# RTCRpi.net
KiCad netlist of a schematic drawn in EAGLE
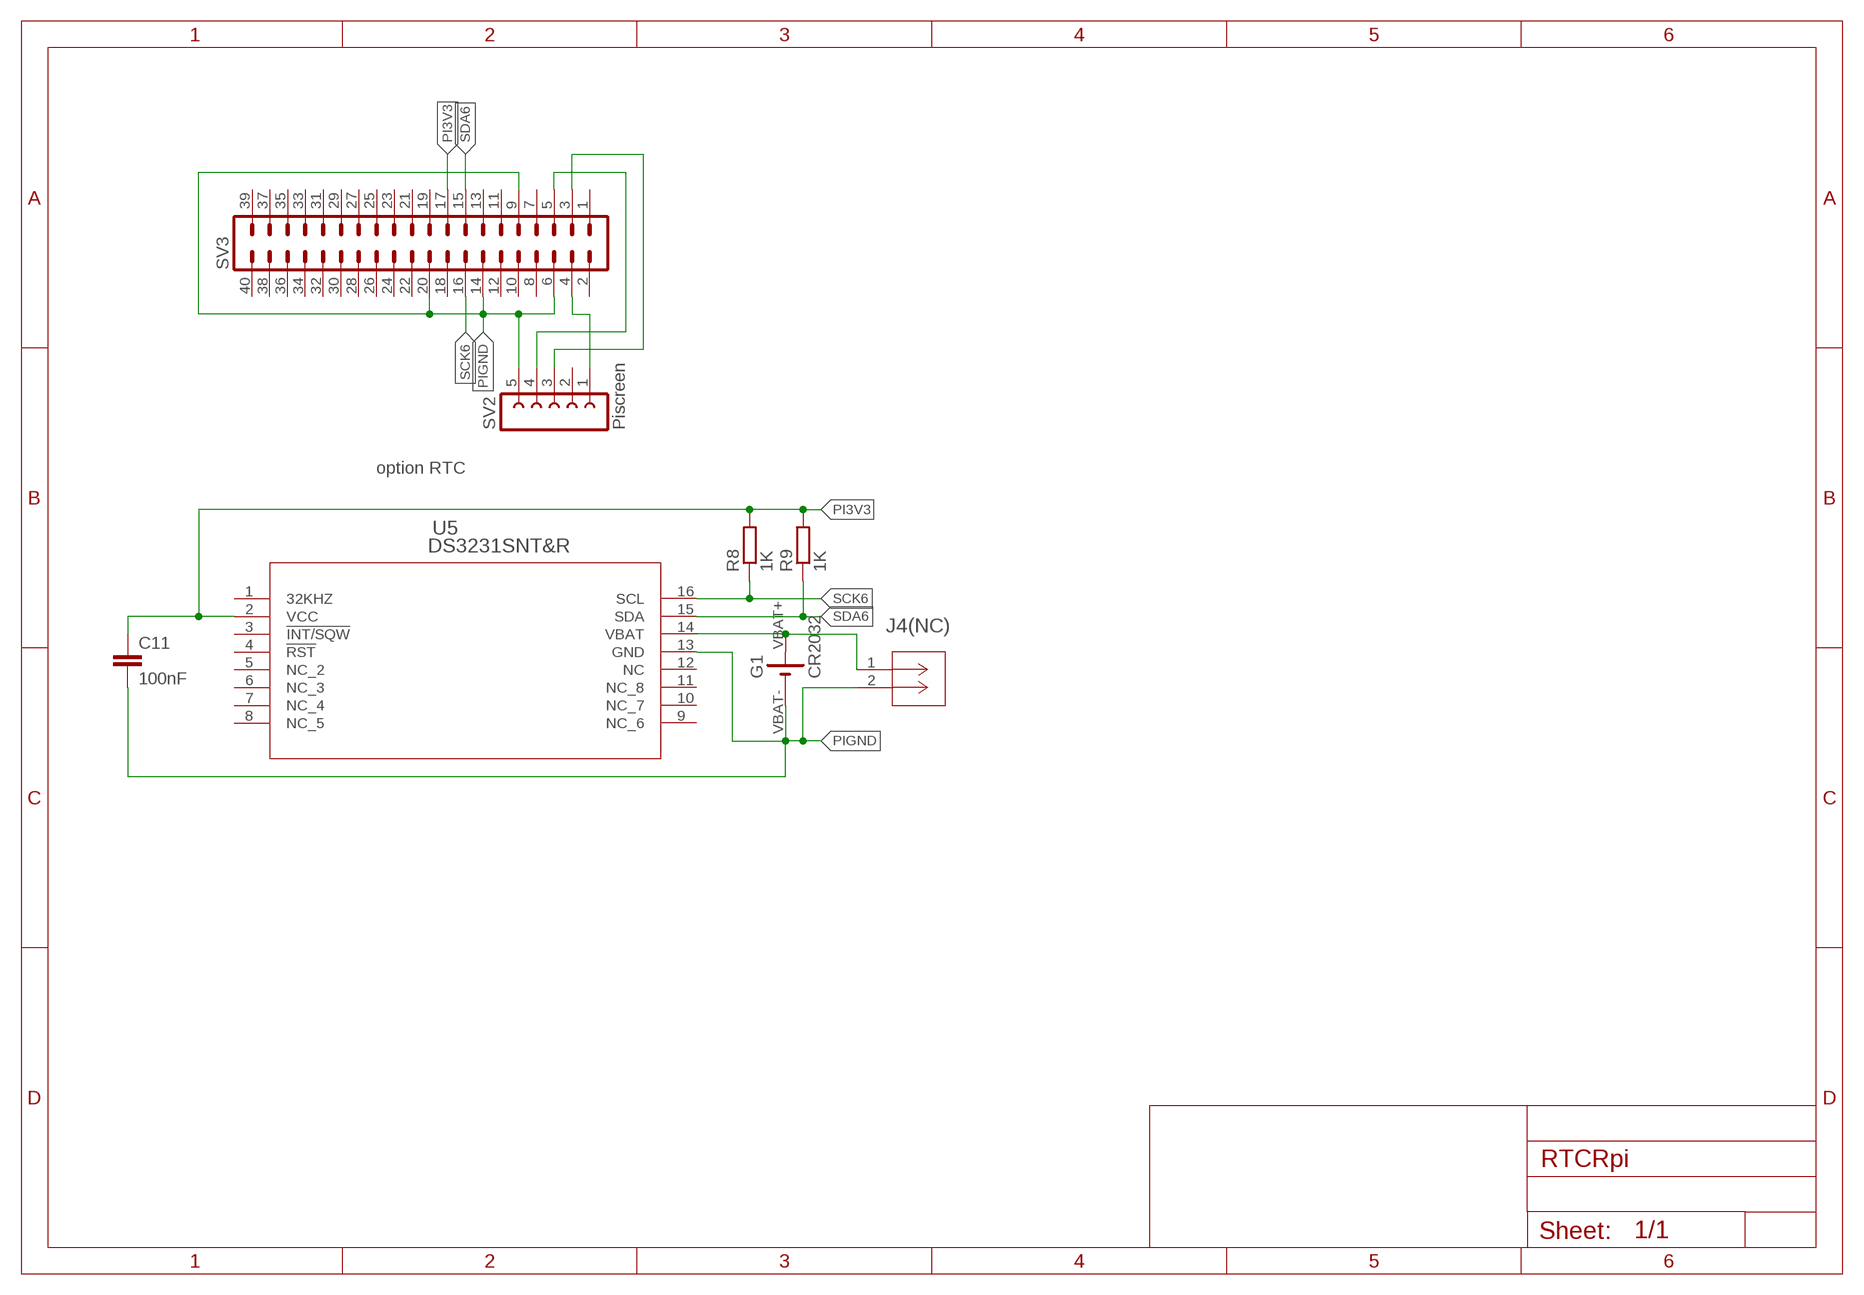
[diagram p0: schematic, sheet 1]

(export (version "E")
  (design (tool "Eeschema 10.0.6"))
  (components
    (comp (ref "C11")
      (value "100nF")
      (footprint "eagle-import:C0603K")
      (libsource (lib "eagle-import") (part "C-EUC0603K"))
    )
    (comp (ref "G1")
      (value "CR2032")
      (footprint "eagle-import:CR2032")
      (libsource (lib "eagle-import") (part "CR2032"))
    )
    (comp (ref "J4(NC)")
      (value "B2B-XH-A(LF)(SN)")
      (footprint "eagle-import:CONN_B2B-XH-A(LF)(SN)_JST")
      (fields (field (name "COPYRIGHT") "Copyright (C) 2018 Accelerated Designs. All rights reserved"))
      (libsource (lib "eagle-import") (part "B2B-XH-A(LF)(SN)"))
    )
    (comp (ref "R8")
      (value "1K")
      (footprint "eagle-import:R0805")
      (libsource (lib "eagle-import") (part "R-EU_R0805"))
    )
    (comp (ref "R9")
      (value "1K")
      (footprint "eagle-import:R0805")
      (libsource (lib "eagle-import") (part "R-EU_R0805"))
    )
    (comp (ref "SV2")
      (value "Piscreen")
      (footprint "eagle-import:FE05-1")
      (libsource (lib "eagle-import") (part "FE05-1"))
    )
    (comp (ref "SV3")
      (value "MA20-2")
      (footprint "eagle-import:MA20-2")
      (libsource (lib "eagle-import") (part "MA20-2"))
    )
    (comp (ref "U5")
      (value "DS3231SNT&R")
      (footprint "eagle-import:21-0042B_16_MXM")
      (fields (field (name "MANUFACTURER_PART_NUMBER") "DS3231SN#T&R"))
      (libsource (lib "eagle-import") (part "DS3231SNT&R"))
    )
  )
  (nets
    (net (code "1") (name "Net-(G1-+)") (class "Default")
      (node (ref "G1") (pin "VBAT+") (pinfunction "+_VBAT+") (pintype "passive"))
      (node (ref "J4(NC)") (pin "1") (pinfunction "1_1") (pintype "passive"))
      (node (ref "U5") (pin "14") (pinfunction "VBAT_14") (pintype "power_in"))
    )
    (net (code "2") (name "Net-(SV2-Pad1)") (class "Default")
      (node (ref "SV2") (pin "1") (pinfunction "1_1") (pintype "passive"))
      (node (ref "SV3") (pin "4") (pinfunction "4_4") (pintype "passive"))
    )
    (net (code "3") (name "Net-(SV2-Pad3)") (class "Default")
      (node (ref "SV2") (pin "3") (pinfunction "3_3") (pintype "passive"))
      (node (ref "SV3") (pin "3") (pinfunction "3_3") (pintype "passive"))
    )
    (net (code "4") (name "Net-(SV2-Pad4)") (class "Default")
      (node (ref "SV2") (pin "4") (pinfunction "4_4") (pintype "passive"))
      (node (ref "SV3") (pin "5") (pinfunction "5_5") (pintype "passive"))
    )
    (net (code "5") (name "PI3V3") (class "Default")
      (node (ref "C11") (pin "1") (pinfunction "1_1") (pintype "passive"))
      (node (ref "R8") (pin "2") (pinfunction "2_2") (pintype "passive"))
      (node (ref "R9") (pin "2") (pinfunction "2_2") (pintype "passive"))
      (node (ref "SV3") (pin "17") (pinfunction "17_17") (pintype "passive"))
      (node (ref "U5") (pin "2") (pinfunction "VCC_2") (pintype "power_in"))
    )
    (net (code "6") (name "PIGND") (class "Default")
      (node (ref "C11") (pin "2") (pinfunction "2_2") (pintype "passive"))
      (node (ref "G1") (pin "VBAT-") (pinfunction "-_VBAT-") (pintype "passive"))
      (node (ref "J4(NC)") (pin "2") (pinfunction "2_2") (pintype "passive"))
      (node (ref "SV2") (pin "5") (pinfunction "5_5") (pintype "passive"))
      (node (ref "SV3") (pin "14") (pinfunction "14_14") (pintype "passive"))
      (node (ref "SV3") (pin "20") (pinfunction "20_20") (pintype "passive"))
      (node (ref "SV3") (pin "6") (pinfunction "6_6") (pintype "passive"))
      (node (ref "SV3") (pin "9") (pinfunction "9_9") (pintype "passive"))
      (node (ref "U5") (pin "13") (pinfunction "GND_13") (pintype "power_in"))
    )
    (net (code "7") (name "SCK6") (class "Default")
      (node (ref "R8") (pin "1") (pinfunction "1_1") (pintype "passive"))
      (node (ref "SV3") (pin "16") (pinfunction "16_16") (pintype "passive"))
      (node (ref "U5") (pin "16") (pinfunction "SCL_16") (pintype "passive"))
    )
    (net (code "8") (name "SDA6") (class "Default")
      (node (ref "R9") (pin "1") (pinfunction "1_1") (pintype "passive"))
      (node (ref "SV3") (pin "15") (pinfunction "15_15") (pintype "passive"))
      (node (ref "U5") (pin "15") (pinfunction "SDA_15") (pintype "passive"))
    )
    (net (code "9") (name "unconnected-(SV2-Pad2)") (class "Default")
      (node (ref "SV2") (pin "2") (pinfunction "2_2") (pintype "passive"))
    )
    (net (code "10") (name "unconnected-(SV3-Pad1)") (class "Default")
      (node (ref "SV3") (pin "1") (pinfunction "1_1") (pintype "passive"))
    )
    (net (code "11") (name "unconnected-(SV3-Pad2)") (class "Default")
      (node (ref "SV3") (pin "2") (pinfunction "2_2") (pintype "passive"))
    )
    (net (code "12") (name "unconnected-(SV3-Pad7)") (class "Default")
      (node (ref "SV3") (pin "7") (pinfunction "7_7") (pintype "passive"))
    )
    (net (code "13") (name "unconnected-(SV3-Pad8)") (class "Default")
      (node (ref "SV3") (pin "8") (pinfunction "8_8") (pintype "passive"))
    )
    (net (code "14") (name "unconnected-(SV3-Pad10)") (class "Default")
      (node (ref "SV3") (pin "10") (pinfunction "10_10") (pintype "passive"))
    )
    (net (code "15") (name "unconnected-(SV3-Pad11)") (class "Default")
      (node (ref "SV3") (pin "11") (pinfunction "11_11") (pintype "passive"))
    )
    (net (code "16") (name "unconnected-(SV3-Pad12)") (class "Default")
      (node (ref "SV3") (pin "12") (pinfunction "12_12") (pintype "passive"))
    )
    (net (code "17") (name "unconnected-(SV3-Pad13)") (class "Default")
      (node (ref "SV3") (pin "13") (pinfunction "13_13") (pintype "passive"))
    )
    (net (code "18") (name "unconnected-(SV3-Pad18)") (class "Default")
      (node (ref "SV3") (pin "18") (pinfunction "18_18") (pintype "passive"))
    )
    (net (code "19") (name "unconnected-(SV3-Pad19)") (class "Default")
      (node (ref "SV3") (pin "19") (pinfunction "19_19") (pintype "passive"))
    )
    (net (code "20") (name "unconnected-(SV3-Pad21)") (class "Default")
      (node (ref "SV3") (pin "21") (pinfunction "21_21") (pintype "passive"))
    )
    (net (code "21") (name "unconnected-(SV3-Pad22)") (class "Default")
      (node (ref "SV3") (pin "22") (pinfunction "22_22") (pintype "passive"))
    )
    (net (code "22") (name "unconnected-(SV3-Pad23)") (class "Default")
      (node (ref "SV3") (pin "23") (pinfunction "23_23") (pintype "passive"))
    )
    (net (code "23") (name "unconnected-(SV3-Pad24)") (class "Default")
      (node (ref "SV3") (pin "24") (pinfunction "24_24") (pintype "passive"))
    )
    (net (code "24") (name "unconnected-(SV3-Pad25)") (class "Default")
      (node (ref "SV3") (pin "25") (pinfunction "25_25") (pintype "passive"))
    )
    (net (code "25") (name "unconnected-(SV3-Pad26)") (class "Default")
      (node (ref "SV3") (pin "26") (pinfunction "26_26") (pintype "passive"))
    )
    (net (code "26") (name "unconnected-(SV3-Pad27)") (class "Default")
      (node (ref "SV3") (pin "27") (pinfunction "27_27") (pintype "passive"))
    )
    (net (code "27") (name "unconnected-(SV3-Pad28)") (class "Default")
      (node (ref "SV3") (pin "28") (pinfunction "28_28") (pintype "passive"))
    )
    (net (code "28") (name "unconnected-(SV3-Pad29)") (class "Default")
      (node (ref "SV3") (pin "29") (pinfunction "29_29") (pintype "passive"))
    )
    (net (code "29") (name "unconnected-(SV3-Pad30)") (class "Default")
      (node (ref "SV3") (pin "30") (pinfunction "30_30") (pintype "passive"))
    )
    (net (code "30") (name "unconnected-(SV3-Pad31)") (class "Default")
      (node (ref "SV3") (pin "31") (pinfunction "31_31") (pintype "passive"))
    )
    (net (code "31") (name "unconnected-(SV3-Pad32)") (class "Default")
      (node (ref "SV3") (pin "32") (pinfunction "32_32") (pintype "passive"))
    )
    (net (code "32") (name "unconnected-(SV3-Pad33)") (class "Default")
      (node (ref "SV3") (pin "33") (pinfunction "33_33") (pintype "passive"))
    )
    (net (code "33") (name "unconnected-(SV3-Pad34)") (class "Default")
      (node (ref "SV3") (pin "34") (pinfunction "34_34") (pintype "passive"))
    )
    (net (code "34") (name "unconnected-(SV3-Pad35)") (class "Default")
      (node (ref "SV3") (pin "35") (pinfunction "35_35") (pintype "passive"))
    )
    (net (code "35") (name "unconnected-(SV3-Pad36)") (class "Default")
      (node (ref "SV3") (pin "36") (pinfunction "36_36") (pintype "passive"))
    )
    (net (code "36") (name "unconnected-(SV3-Pad37)") (class "Default")
      (node (ref "SV3") (pin "37") (pinfunction "37_37") (pintype "passive"))
    )
    (net (code "37") (name "unconnected-(SV3-Pad38)") (class "Default")
      (node (ref "SV3") (pin "38") (pinfunction "38_38") (pintype "passive"))
    )
    (net (code "38") (name "unconnected-(SV3-Pad39)") (class "Default")
      (node (ref "SV3") (pin "39") (pinfunction "39_39") (pintype "passive"))
    )
    (net (code "39") (name "unconnected-(SV3-Pad40)") (class "Default")
      (node (ref "SV3") (pin "40") (pinfunction "40_40") (pintype "passive"))
    )
    (net (code "40") (name "unconnected-(U5-32KHZ-Pad1)") (class "Default")
      (node (ref "U5") (pin "1") (pinfunction "32KHZ_1") (pintype "passive"))
    )
    (net (code "41") (name "unconnected-(U5-NC-Pad12)") (class "Default")
      (node (ref "U5") (pin "12") (pinfunction "NC_12") (pintype "passive"))
    )
    (net (code "42") (name "unconnected-(U5-NC_2-Pad5)") (class "Default")
      (node (ref "U5") (pin "5") (pinfunction "NC_2_5") (pintype "passive"))
    )
    (net (code "43") (name "unconnected-(U5-NC_3-Pad6)") (class "Default")
      (node (ref "U5") (pin "6") (pinfunction "NC_3_6") (pintype "passive"))
    )
    (net (code "44") (name "unconnected-(U5-NC_4-Pad7)") (class "Default")
      (node (ref "U5") (pin "7") (pinfunction "NC_4_7") (pintype "passive"))
    )
    (net (code "45") (name "unconnected-(U5-NC_5-Pad8)") (class "Default")
      (node (ref "U5") (pin "8") (pinfunction "NC_5_8") (pintype "passive"))
    )
    (net (code "46") (name "unconnected-(U5-NC_6-Pad9)") (class "Default")
      (node (ref "U5") (pin "9") (pinfunction "NC_6_9") (pintype "passive"))
    )
    (net (code "47") (name "unconnected-(U5-NC_7-Pad10)") (class "Default")
      (node (ref "U5") (pin "10") (pinfunction "NC_7_10") (pintype "passive"))
    )
    (net (code "48") (name "unconnected-(U5-NC_8-Pad11)") (class "Default")
      (node (ref "U5") (pin "11") (pinfunction "NC_8_11") (pintype "passive"))
    )
    (net (code "49") (name "unconnected-(U5-~{INT{slash}SQW}-Pad3)") (class "Default")
      (node (ref "U5") (pin "3") (pinfunction "~{INT/SQW}_3") (pintype "passive"))
    )
    (net (code "50") (name "unconnected-(U5-~{RST}-Pad4)") (class "Default")
      (node (ref "U5") (pin "4") (pinfunction "~{RST}_4") (pintype "passive"))
    )
  )
)
